# Top.net
KiCad netlist of a schematic drawn in Altium Designer
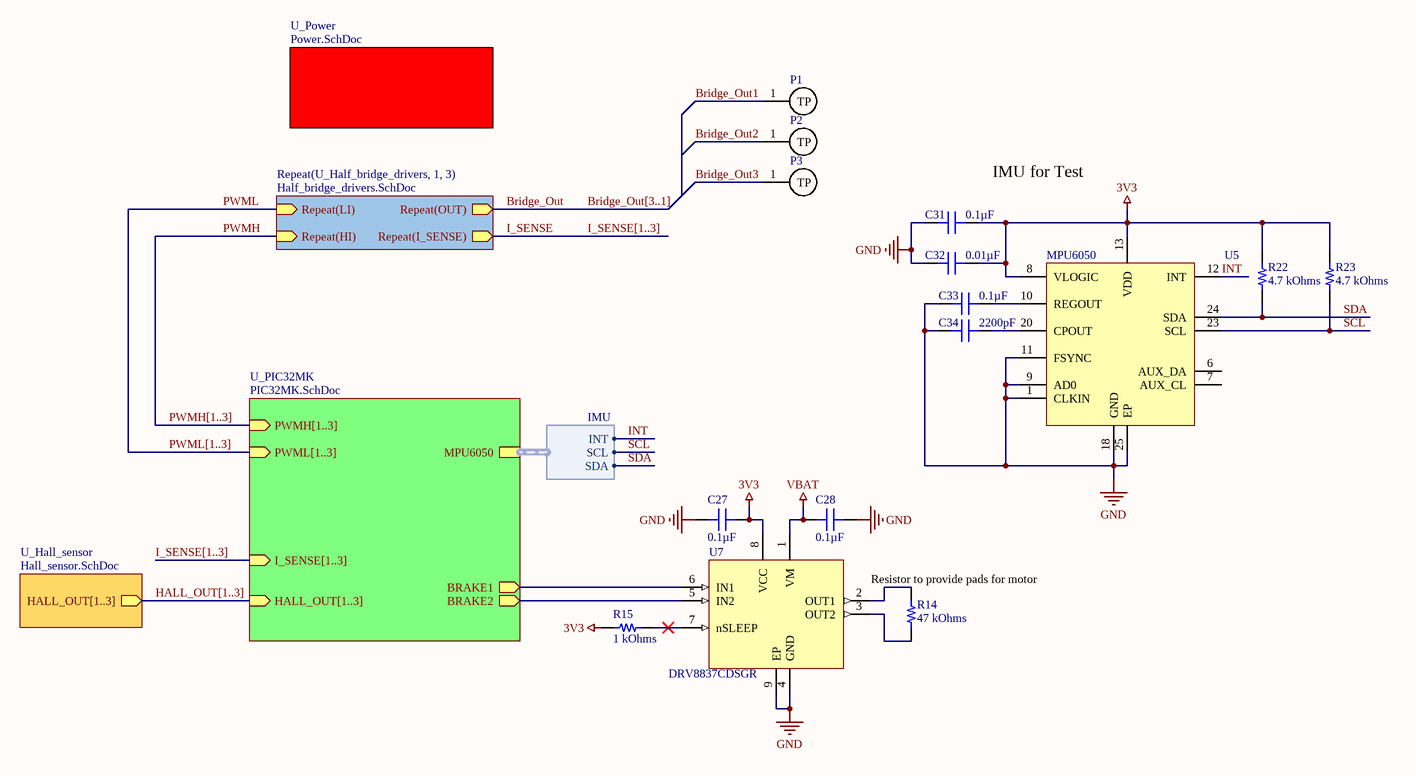
[diagram p0: Top.SchDoc]

(export (version "E")
  (design (tool "Eeschema 10.0.6"))
  (components
    (comp (ref "C27")
      (value "0.1µF")
      (footprint "CAP 0603_1608")
      (description "CAP CER 0.1UF 100V 0603 EPOXY")
      (fields
        (field (name "PART NUMBER") "GCG188R92A104KA03D")
        (field (name "MANUFACTURER") "Murata Electronics")
      )
      (libsource (lib "Celestial Altium Library - altium_library") (part "Capacitor"))
    )
    (comp (ref "C28")
      (value "0.1µF")
      (footprint "CAP 0603_1608")
      (description "CAP CER 0.1UF 100V 0603 EPOXY")
      (fields
        (field (name "PART NUMBER") "GCG188R92A104KA03D")
        (field (name "MANUFACTURER") "Murata Electronics")
      )
      (libsource (lib "Celestial Altium Library - altium_library") (part "Capacitor"))
    )
    (comp (ref "C31")
      (value "0.1µF")
      (footprint "CAP 0603_1608")
      (description "CAP CER 0.1UF 100V 0603 EPOXY")
      (fields
        (field (name "PART NUMBER") "GCG188R92A104KA03D")
        (field (name "MANUFACTURER") "Murata Electronics")
      )
      (libsource (lib "Celestial Altium Library - altium_library") (part "Capacitor"))
    )
    (comp (ref "C32")
      (value "0.01µF")
      (footprint "CAP 0603_1608")
      (description "CAP CER 0.01UF 250V X7R 0603")
      (fields (field (name "PART NUMBER") "C0603C103KARACAUTO") (field (name "MANUFACTURER") "KEMET"))
      (libsource (lib "Celestial Altium Library - altium_library") (part "Capacitor"))
    )
    (comp (ref "C33")
      (value "0.1µF")
      (footprint "CAP 0603_1608")
      (description "CAP CER 0.1UF 100V 0603 EPOXY")
      (fields
        (field (name "PART NUMBER") "GCG188R92A104KA03D")
        (field (name "MANUFACTURER") "Murata Electronics")
      )
      (libsource (lib "Celestial Altium Library - altium_library") (part "Capacitor"))
    )
    (comp (ref "C34")
      (value "2200pF")
      (footprint "CAP 0603_1608")
      (description "CAP CER 2200PF 50V 0603 EPOXY")
      (fields
        (field (name "PART NUMBER") "CGA3E2X8R1H222M080AD")
        (field (name "MANUFACTURER") "TDK Corporation")
      )
      (libsource (lib "Celestial Altium Library - altium_library") (part "Capacitor"))
    )
    (comp (ref "P1") (value "TP") (footprint "2mmHole") (libsource (lib "IC") (part "TP")))
    (comp (ref "P2") (value "TP") (footprint "2mmHole") (libsource (lib "IC") (part "TP")))
    (comp (ref "P3") (value "TP") (footprint "2mmHole") (libsource (lib "IC") (part "TP")))
    (comp (ref "R14")
      (value "47 kOhms")
      (footprint "RES 2512_6432")
      (description "RES 47K OHM 5% 1W 2512")
      (fields
        (field (name "PART NUMBER") "RK73B3ATTE473J")
        (field (name "MANUFACTURER") "KOA Speer Electronics, Inc.")
      )
      (libsource (lib "Celestial Altium Library - altium_library") (part "Resistor"))
    )
    (comp (ref "R15")
      (value "1 kOhms")
      (footprint "RES 0603_1608")
      (description "RES SMD 1K OHM 1% 1/10W 0603")
      (fields (field (name "PART NUMBER") "RT0603FRE071KL") (field (name "MANUFACTURER") "Yageo"))
      (libsource (lib "Celestial Altium Library - altium_library") (part "Resistor"))
    )
    (comp (ref "R22")
      (value "4.7 kOhms")
      (footprint "RES 0603_1608")
      (description "RES SMD 4.7K OHM 0.1% 1/16W 0603")
      (fields
        (field (name "PART NUMBER") "CPF-A-0603B4K7E")
        (field (name "MANUFACTURER") "TE Connectivity Passive Product")
      )
      (libsource (lib "Celestial Altium Library - altium_library") (part "Resistor"))
    )
    (comp (ref "R23")
      (value "4.7 kOhms")
      (footprint "RES 0603_1608")
      (description "RES SMD 4.7K OHM 0.1% 1/16W 0603")
      (fields
        (field (name "PART NUMBER") "CPF-A-0603B4K7E")
        (field (name "MANUFACTURER") "TE Connectivity Passive Product")
      )
      (libsource (lib "Celestial Altium Library - altium_library") (part "Resistor"))
    )
    (comp (ref "U5") (value "MPU6050") (footprint "IC_MPU6050") (libsource (lib "IC") (part "MPU6050")))
    (comp (ref "U7")
      (value "DRV8837CDSGR")
      (footprint "SON50P200X200X80-9N")
      (description "11-V, 1-A H-bridge motor driver 8-WSON -40 to 85")
      (fields (field (name "MF") "Texas Instruments"))
      (libsource (lib "IC") (part "DRV8837CDSGR"))
    )
  )
  (nets
    (net (code "14") (name "/BRAKE1") (class "Default")
      (node (ref "U7") (pin "6") (pinfunction "IN1_6") (pintype "input"))
    )
    (net (code "15") (name "/BRAKE2") (class "Default")
      (node (ref "U7") (pin "5") (pinfunction "IN2_5") (pintype "input"))
    )
    (net (code "17") (name "/Bridge_Out1") (class "Default")
      (node (ref "P1") (pin "1") (pinfunction "TP_1") (pintype "passive"))
    )
    (net (code "18") (name "/Bridge_Out2") (class "Default")
      (node (ref "P2") (pin "1") (pinfunction "TP_1") (pintype "passive"))
    )
    (net (code "19") (name "/Bridge_Out3") (class "Default")
      (node (ref "P3") (pin "1") (pinfunction "TP_1") (pintype "passive"))
    )
    (net (code "22") (name "/INT") (class "Default")
      (node (ref "U5") (pin "12") (pinfunction "INT_12") (pintype "passive"))
    )
    (net (code "29") (name "/SCL") (class "Default")
      (node (ref "R23") (pin "1") (pinfunction "1_1") (pintype "passive"))
      (node (ref "U5") (pin "23") (pinfunction "SCL_23") (pintype "passive"))
    )
    (net (code "30") (name "/SDA") (class "Default")
      (node (ref "R22") (pin "1") (pinfunction "1_1") (pintype "passive"))
      (node (ref "U5") (pin "24") (pinfunction "SDA_24") (pintype "passive"))
    )
    (net (code "32") (name "3V3") (class "Default")
      (node (ref "C27") (pin "2") (pinfunction "2_2") (pintype "passive"))
      (node (ref "C31") (pin "2") (pinfunction "2_2") (pintype "passive"))
      (node (ref "C32") (pin "2") (pinfunction "2_2") (pintype "passive"))
      (node (ref "R15") (pin "2") (pinfunction "2_2") (pintype "passive"))
      (node (ref "R22") (pin "2") (pinfunction "2_2") (pintype "passive"))
      (node (ref "R23") (pin "2") (pinfunction "2_2") (pintype "passive"))
      (node (ref "U5") (pin "13") (pinfunction "VDD_13") (pintype "passive"))
      (node (ref "U5") (pin "8") (pinfunction "VLOGIC_8") (pintype "passive"))
      (node (ref "U7") (pin "8") (pinfunction "VCC_8") (pintype "power_in"))
    )
    (net (code "33") (name "GND") (class "Default")
      (node (ref "C27") (pin "1") (pinfunction "1_1") (pintype "passive"))
      (node (ref "C28") (pin "2") (pinfunction "2_2") (pintype "passive"))
      (node (ref "C31") (pin "1") (pinfunction "1_1") (pintype "passive"))
      (node (ref "C32") (pin "1") (pinfunction "1_1") (pintype "passive"))
      (node (ref "C33") (pin "2") (pinfunction "2_2") (pintype "passive"))
      (node (ref "C34") (pin "2") (pinfunction "2_2") (pintype "passive"))
      (node (ref "U5") (pin "1") (pinfunction "CLKIN_1") (pintype "passive"))
      (node (ref "U5") (pin "11") (pinfunction "FSYNC_11") (pintype "passive"))
      (node (ref "U5") (pin "18") (pinfunction "GND_18") (pintype "passive"))
      (node (ref "U5") (pin "25") (pinfunction "EP_25") (pintype "passive"))
      (node (ref "U5") (pin "9") (pinfunction "AD0_9") (pintype "passive"))
      (node (ref "U7") (pin "4") (pinfunction "GND_4") (pintype "power_in"))
      (node (ref "U7") (pin "9") (pinfunction "EP_9") (pintype "power_in"))
    )
    (net (code "34") (name "Net-(U5-CPOUT)") (class "Default")
      (node (ref "C34") (pin "1") (pinfunction "1_1") (pintype "passive"))
      (node (ref "U5") (pin "20") (pinfunction "CPOUT_20") (pintype "passive"))
    )
    (net (code "35") (name "Net-(U5-REGOUT)") (class "Default")
      (node (ref "C33") (pin "1") (pinfunction "1_1") (pintype "passive"))
      (node (ref "U5") (pin "10") (pinfunction "REGOUT_10") (pintype "passive"))
    )
    (net (code "36") (name "Net-(U7-OUT1)") (class "Default")
      (node (ref "R14") (pin "1") (pinfunction "1_1") (pintype "passive"))
      (node (ref "U7") (pin "2") (pinfunction "OUT1_2") (pintype "output"))
    )
    (net (code "37") (name "Net-(U7-OUT2)") (class "Default")
      (node (ref "R14") (pin "2") (pinfunction "2_2") (pintype "passive"))
      (node (ref "U7") (pin "3") (pinfunction "OUT2_3") (pintype "output"))
    )
    (net (code "38") (name "Net-(U7-nSLEEP)") (class "Default")
      (node (ref "R15") (pin "1") (pinfunction "1_1") (pintype "passive"))
      (node (ref "U7") (pin "7") (pinfunction "nSLEEP_7") (pintype "input"))
    )
    (net (code "39") (name "VBAT") (class "Default")
      (node (ref "C28") (pin "1") (pinfunction "1_1") (pintype "passive"))
      (node (ref "U7") (pin "1") (pinfunction "VM_1") (pintype "power_in"))
    )
    (net (code "40") (name "unconnected-(U5-AUX_CL-Pad7)") (class "Default")
      (node (ref "U5") (pin "7") (pinfunction "AUX_CL_7") (pintype "passive"))
    )
    (net (code "41") (name "unconnected-(U5-AUX_DA-Pad6)") (class "Default")
      (node (ref "U5") (pin "6") (pinfunction "AUX_DA_6") (pintype "passive"))
    )
  )
)
